# Consumer.net
KiCad netlist of a schematic drawn in Altium Designer
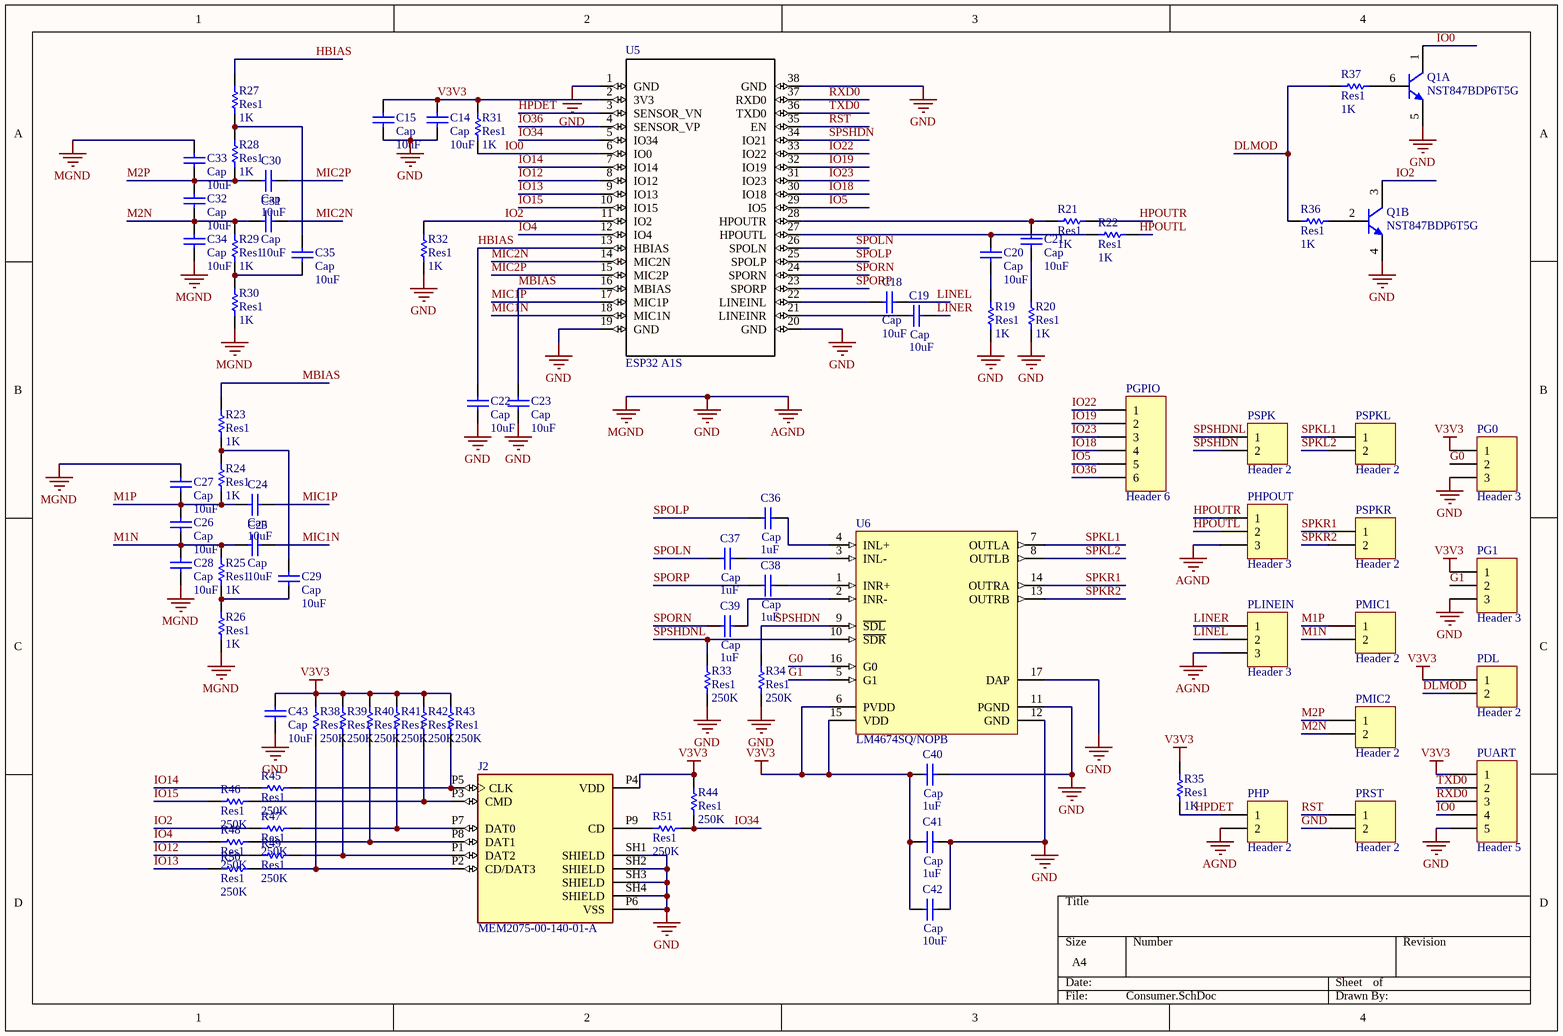
[diagram p0: Consumer.SchDoc]

(export (version "E")
  (design (tool "Eeschema 10.0.6"))
  (components
    (comp (ref "C14")
      (value "Cap")
      (footprint "1812")
      (description "Capacitor")
      (fields (field (name "ALTIUM_VALUE") "10uF") (field (name "PUBLISHER") "Altium Limited"))
      (libsource (lib "Miscellaneous Devices") (part "Cap"))
    )
    (comp (ref "C15")
      (value "Cap")
      (footprint "1608[0603]")
      (description "Capacitor")
      (fields (field (name "ALTIUM_VALUE") "10uF") (field (name "PUBLISHER") "Altium Limited"))
      (libsource (lib "Miscellaneous Devices") (part "Cap"))
    )
    (comp (ref "C18")
      (value "Cap")
      (footprint "1608[0603]")
      (description "Capacitor")
      (fields (field (name "ALTIUM_VALUE") "10uF") (field (name "PUBLISHER") "Altium Limited"))
      (libsource (lib "Miscellaneous Devices") (part "Cap"))
    )
    (comp (ref "C19")
      (value "Cap")
      (footprint "1608[0603]")
      (description "Capacitor")
      (fields (field (name "ALTIUM_VALUE") "10uF") (field (name "PUBLISHER") "Altium Limited"))
      (libsource (lib "Miscellaneous Devices") (part "Cap"))
    )
    (comp (ref "C20")
      (value "Cap")
      (footprint "1608[0603]")
      (description "Capacitor")
      (fields (field (name "ALTIUM_VALUE") "10uF") (field (name "PUBLISHER") "Altium Limited"))
      (libsource (lib "Miscellaneous Devices") (part "Cap"))
    )
    (comp (ref "C21")
      (value "Cap")
      (footprint "1608[0603]")
      (description "Capacitor")
      (fields (field (name "ALTIUM_VALUE") "10uF") (field (name "PUBLISHER") "Altium Limited"))
      (libsource (lib "Miscellaneous Devices") (part "Cap"))
    )
    (comp (ref "C22")
      (value "Cap")
      (footprint "1608[0603]")
      (description "Capacitor")
      (fields (field (name "ALTIUM_VALUE") "10uF") (field (name "PUBLISHER") "Altium Limited"))
      (libsource (lib "Miscellaneous Devices") (part "Cap"))
    )
    (comp (ref "C23")
      (value "Cap")
      (footprint "1608[0603]")
      (description "Capacitor")
      (fields (field (name "ALTIUM_VALUE") "10uF") (field (name "PUBLISHER") "Altium Limited"))
      (libsource (lib "Miscellaneous Devices") (part "Cap"))
    )
    (comp (ref "C24")
      (value "Cap")
      (footprint "1608[0603]")
      (description "Capacitor")
      (fields (field (name "ALTIUM_VALUE") "10uF") (field (name "PUBLISHER") "Altium Limited"))
      (libsource (lib "Miscellaneous Devices") (part "Cap"))
    )
    (comp (ref "C25")
      (value "Cap")
      (footprint "1608[0603]")
      (description "Capacitor")
      (fields (field (name "ALTIUM_VALUE") "10uF") (field (name "PUBLISHER") "Altium Limited"))
      (libsource (lib "Miscellaneous Devices") (part "Cap"))
    )
    (comp (ref "C26")
      (value "Cap")
      (footprint "1608[0603]")
      (description "Capacitor")
      (fields (field (name "ALTIUM_VALUE") "10uF") (field (name "PUBLISHER") "Altium Limited"))
      (libsource (lib "Miscellaneous Devices") (part "Cap"))
    )
    (comp (ref "C27")
      (value "Cap")
      (footprint "1608[0603]")
      (description "Capacitor")
      (fields (field (name "ALTIUM_VALUE") "10uF") (field (name "PUBLISHER") "Altium Limited"))
      (libsource (lib "Miscellaneous Devices") (part "Cap"))
    )
    (comp (ref "C28")
      (value "Cap")
      (footprint "1608[0603]")
      (description "Capacitor")
      (fields (field (name "ALTIUM_VALUE") "10uF") (field (name "PUBLISHER") "Altium Limited"))
      (libsource (lib "Miscellaneous Devices") (part "Cap"))
    )
    (comp (ref "C29")
      (value "Cap")
      (footprint "1608[0603]")
      (description "Capacitor")
      (fields (field (name "ALTIUM_VALUE") "10uF") (field (name "PUBLISHER") "Altium Limited"))
      (libsource (lib "Miscellaneous Devices") (part "Cap"))
    )
    (comp (ref "C30")
      (value "Cap")
      (footprint "1608[0603]")
      (description "Capacitor")
      (fields (field (name "ALTIUM_VALUE") "10uF") (field (name "PUBLISHER") "Altium Limited"))
      (libsource (lib "Miscellaneous Devices") (part "Cap"))
    )
    (comp (ref "C31")
      (value "Cap")
      (footprint "1608[0603]")
      (description "Capacitor")
      (fields (field (name "ALTIUM_VALUE") "10uF") (field (name "PUBLISHER") "Altium Limited"))
      (libsource (lib "Miscellaneous Devices") (part "Cap"))
    )
    (comp (ref "C32")
      (value "Cap")
      (footprint "1608[0603]")
      (description "Capacitor")
      (fields (field (name "ALTIUM_VALUE") "10uF") (field (name "PUBLISHER") "Altium Limited"))
      (libsource (lib "Miscellaneous Devices") (part "Cap"))
    )
    (comp (ref "C33")
      (value "Cap")
      (footprint "1608[0603]")
      (description "Capacitor")
      (fields (field (name "ALTIUM_VALUE") "10uF") (field (name "PUBLISHER") "Altium Limited"))
      (libsource (lib "Miscellaneous Devices") (part "Cap"))
    )
    (comp (ref "C34")
      (value "Cap")
      (footprint "1608[0603]")
      (description "Capacitor")
      (fields (field (name "ALTIUM_VALUE") "10uF") (field (name "PUBLISHER") "Altium Limited"))
      (libsource (lib "Miscellaneous Devices") (part "Cap"))
    )
    (comp (ref "C35")
      (value "Cap")
      (footprint "1608[0603]")
      (description "Capacitor")
      (fields (field (name "ALTIUM_VALUE") "10uF") (field (name "PUBLISHER") "Altium Limited"))
      (libsource (lib "Miscellaneous Devices") (part "Cap"))
    )
    (comp (ref "C36")
      (value "Cap")
      (footprint "1608[0603]")
      (description "Capacitor")
      (fields (field (name "ALTIUM_VALUE") "1uF") (field (name "PUBLISHER") "Altium Limited"))
      (libsource (lib "Miscellaneous Devices") (part "Cap"))
    )
    (comp (ref "C37")
      (value "Cap")
      (footprint "1608[0603]")
      (description "Capacitor")
      (fields (field (name "ALTIUM_VALUE") "1uF") (field (name "PUBLISHER") "Altium Limited"))
      (libsource (lib "Miscellaneous Devices") (part "Cap"))
    )
    (comp (ref "C38")
      (value "Cap")
      (footprint "1608[0603]")
      (description "Capacitor")
      (fields (field (name "ALTIUM_VALUE") "1uF") (field (name "PUBLISHER") "Altium Limited"))
      (libsource (lib "Miscellaneous Devices") (part "Cap"))
    )
    (comp (ref "C39")
      (value "Cap")
      (footprint "1608[0603]")
      (description "Capacitor")
      (fields (field (name "ALTIUM_VALUE") "1uF") (field (name "PUBLISHER") "Altium Limited"))
      (libsource (lib "Miscellaneous Devices") (part "Cap"))
    )
    (comp (ref "C40")
      (value "Cap")
      (footprint "1608[0603]")
      (description "Capacitor")
      (fields (field (name "ALTIUM_VALUE") "1uF") (field (name "PUBLISHER") "Altium Limited"))
      (libsource (lib "Miscellaneous Devices") (part "Cap"))
    )
    (comp (ref "C41")
      (value "Cap")
      (footprint "1608[0603]")
      (description "Capacitor")
      (fields (field (name "ALTIUM_VALUE") "1uF") (field (name "PUBLISHER") "Altium Limited"))
      (libsource (lib "Miscellaneous Devices") (part "Cap"))
    )
    (comp (ref "C42")
      (value "Cap")
      (footprint "1608[0603]")
      (description "Capacitor")
      (fields (field (name "ALTIUM_VALUE") "10uF") (field (name "PUBLISHER") "Altium Limited"))
      (libsource (lib "Miscellaneous Devices") (part "Cap"))
    )
    (comp (ref "C43")
      (value "Cap")
      (footprint "1608[0603]")
      (description "Capacitor")
      (fields (field (name "ALTIUM_VALUE") "10uF") (field (name "PUBLISHER") "Altium Limited"))
      (libsource (lib "Miscellaneous Devices") (part "Cap"))
    )
    (comp (ref "J2")
      (value "MEM2075-00-140-01-A")
      (footprint "GCT_MEM2075-00-140-01-A")
      (description "9 _8 + 1_ Position Card Connector microSDâ„¢ Surface Mount, Right Angle Gold")
      (fields (field (name "MF") "Global Connector Technology"))
      (libsource (lib "MEM2075-00-140-01-A") (part "MEM2075-00-140-01-A"))
    )
    (comp (ref "PDL")
      (value "Header 2")
      (footprint "HDR1X2")
      (description "Header, 2-Pin")
      (fields (field (name "PUBLISHER") "Altium Limited"))
      (libsource (lib "Miscellaneous Connectors") (part "Header 2"))
    )
    (comp (ref "PG0")
      (value "Header 3")
      (footprint "HDR1X3")
      (description "Header, 3-Pin")
      (fields (field (name "PUBLISHER") "Altium Limited"))
      (libsource (lib "Miscellaneous Connectors") (part "Header 3"))
    )
    (comp (ref "PG1")
      (value "Header 3")
      (footprint "HDR1X3")
      (description "Header, 3-Pin")
      (fields (field (name "PUBLISHER") "Altium Limited"))
      (libsource (lib "Miscellaneous Connectors") (part "Header 3"))
    )
    (comp (ref "PGPIO")
      (value "Header 6")
      (footprint "HDR1X6")
      (description "Header, 6-Pin")
      (fields (field (name "PUBLISHER") "Altium Limited"))
      (libsource (lib "Miscellaneous Connectors") (part "Header 6"))
    )
    (comp (ref "PHP")
      (value "Header 2")
      (footprint "HDR1X2")
      (description "Header, 2-Pin")
      (fields (field (name "PUBLISHER") "Altium Limited"))
      (libsource (lib "Miscellaneous Connectors") (part "Header 2"))
    )
    (comp (ref "PHPOUT")
      (value "Header 3")
      (footprint "HDR1X3")
      (description "Header, 3-Pin")
      (fields (field (name "PUBLISHER") "Altium Limited"))
      (libsource (lib "Miscellaneous Connectors") (part "Header 3"))
    )
    (comp (ref "PLINEIN")
      (value "Header 3")
      (footprint "HDR1X3")
      (description "Header, 3-Pin")
      (fields (field (name "PUBLISHER") "Altium Limited"))
      (libsource (lib "Miscellaneous Connectors") (part "Header 3"))
    )
    (comp (ref "PMIC1")
      (value "Header 2")
      (footprint "HDR1X2")
      (description "Header, 2-Pin")
      (fields (field (name "PUBLISHER") "Altium Limited"))
      (libsource (lib "Miscellaneous Connectors") (part "Header 2"))
    )
    (comp (ref "PMIC2")
      (value "Header 2")
      (footprint "HDR1X2")
      (description "Header, 2-Pin")
      (fields (field (name "PUBLISHER") "Altium Limited"))
      (libsource (lib "Miscellaneous Connectors") (part "Header 2"))
    )
    (comp (ref "PRST")
      (value "Header 2")
      (footprint "HDR1X2")
      (description "Header, 2-Pin")
      (fields (field (name "PUBLISHER") "Altium Limited"))
      (libsource (lib "Miscellaneous Connectors") (part "Header 2"))
    )
    (comp (ref "PSPK")
      (value "Header 2")
      (footprint "HDR1X2")
      (description "Header, 2-Pin")
      (fields (field (name "PUBLISHER") "Altium Limited"))
      (libsource (lib "Miscellaneous Connectors") (part "Header 2"))
    )
    (comp (ref "PSPKL")
      (value "Header 2")
      (footprint "HDR1X2")
      (description "Header, 2-Pin")
      (fields (field (name "PUBLISHER") "Altium Limited"))
      (libsource (lib "Miscellaneous Connectors") (part "Header 2"))
    )
    (comp (ref "PSPKR")
      (value "Header 2")
      (footprint "HDR1X2")
      (description "Header, 2-Pin")
      (fields (field (name "PUBLISHER") "Altium Limited"))
      (libsource (lib "Miscellaneous Connectors") (part "Header 2"))
    )
    (comp (ref "PUART")
      (value "Header 5")
      (footprint "HDR1X5")
      (description "Header, 5-Pin")
      (fields (field (name "PUBLISHER") "Altium Limited"))
      (libsource (lib "Miscellaneous Connectors") (part "Header 5"))
    )
    (comp (ref "Q1")
      (value "NST847BDP6T5G")
      (footprint "ONSC-SOT-963-6-527AD-01_B_V")
      (description "Dual General Purpose Transistors, 6-Pin SOT-963, Pb-Free, Tape and Reel")
      (fields (field (name "MANUFACTURER") "On Semiconductor"))
      (libsource (lib "Components - 31.05.21 - 11.16") (part "CMP-1048-01004-1"))
    )
    (comp (ref "R19")
      (value "Res1")
      (footprint "0603R-GENERIC")
      (description "Resistor")
      (fields (field (name "ALTIUM_VALUE") "1K") (field (name "PUBLISHER") "Altium Limited"))
      (libsource (lib "Miscellaneous Devices") (part "Res1"))
    )
    (comp (ref "R20")
      (value "Res1")
      (footprint "0603R-GENERIC")
      (description "Resistor")
      (fields (field (name "ALTIUM_VALUE") "1K") (field (name "PUBLISHER") "Altium Limited"))
      (libsource (lib "Miscellaneous Devices") (part "Res1"))
    )
    (comp (ref "R21")
      (value "Res1")
      (footprint "0603R-GENERIC")
      (description "Resistor")
      (fields (field (name "ALTIUM_VALUE") "1K") (field (name "PUBLISHER") "Altium Limited"))
      (libsource (lib "Miscellaneous Devices") (part "Res1"))
    )
    (comp (ref "R22")
      (value "Res1")
      (footprint "0603R-GENERIC")
      (description "Resistor")
      (fields (field (name "ALTIUM_VALUE") "1K") (field (name "PUBLISHER") "Altium Limited"))
      (libsource (lib "Miscellaneous Devices") (part "Res1"))
    )
    (comp (ref "R23")
      (value "Res1")
      (footprint "0603R-GENERIC")
      (description "Resistor")
      (fields (field (name "ALTIUM_VALUE") "1K") (field (name "PUBLISHER") "Altium Limited"))
      (libsource (lib "Miscellaneous Devices") (part "Res1"))
    )
    (comp (ref "R24")
      (value "Res1")
      (footprint "0603R-GENERIC")
      (description "Resistor")
      (fields (field (name "ALTIUM_VALUE") "1K") (field (name "PUBLISHER") "Altium Limited"))
      (libsource (lib "Miscellaneous Devices") (part "Res1"))
    )
    (comp (ref "R25")
      (value "Res1")
      (footprint "0603R-GENERIC")
      (description "Resistor")
      (fields (field (name "ALTIUM_VALUE") "1K") (field (name "PUBLISHER") "Altium Limited"))
      (libsource (lib "Miscellaneous Devices") (part "Res1"))
    )
    (comp (ref "R26")
      (value "Res1")
      (footprint "0603R-GENERIC")
      (description "Resistor")
      (fields (field (name "ALTIUM_VALUE") "1K") (field (name "PUBLISHER") "Altium Limited"))
      (libsource (lib "Miscellaneous Devices") (part "Res1"))
    )
    (comp (ref "R27")
      (value "Res1")
      (footprint "0603R-GENERIC")
      (description "Resistor")
      (fields (field (name "ALTIUM_VALUE") "1K") (field (name "PUBLISHER") "Altium Limited"))
      (libsource (lib "Miscellaneous Devices") (part "Res1"))
    )
    (comp (ref "R28")
      (value "Res1")
      (footprint "0603R-GENERIC")
      (description "Resistor")
      (fields (field (name "ALTIUM_VALUE") "1K") (field (name "PUBLISHER") "Altium Limited"))
      (libsource (lib "Miscellaneous Devices") (part "Res1"))
    )
    (comp (ref "R29")
      (value "Res1")
      (footprint "0603R-GENERIC")
      (description "Resistor")
      (fields (field (name "ALTIUM_VALUE") "1K") (field (name "PUBLISHER") "Altium Limited"))
      (libsource (lib "Miscellaneous Devices") (part "Res1"))
    )
    (comp (ref "R30")
      (value "Res1")
      (footprint "0603R-GENERIC")
      (description "Resistor")
      (fields (field (name "ALTIUM_VALUE") "1K") (field (name "PUBLISHER") "Altium Limited"))
      (libsource (lib "Miscellaneous Devices") (part "Res1"))
    )
    (comp (ref "R31")
      (value "Res1")
      (footprint "0603R-GENERIC")
      (description "Resistor")
      (fields (field (name "ALTIUM_VALUE") "1K") (field (name "PUBLISHER") "Altium Limited"))
      (libsource (lib "Miscellaneous Devices") (part "Res1"))
    )
    (comp (ref "R32")
      (value "Res1")
      (footprint "0603R-GENERIC")
      (description "Resistor")
      (fields (field (name "ALTIUM_VALUE") "1K") (field (name "PUBLISHER") "Altium Limited"))
      (libsource (lib "Miscellaneous Devices") (part "Res1"))
    )
    (comp (ref "R33")
      (value "Res1")
      (footprint "0603R-GENERIC")
      (description "Resistor")
      (fields (field (name "ALTIUM_VALUE") "250K") (field (name "PUBLISHER") "Altium Limited"))
      (libsource (lib "Miscellaneous Devices") (part "Res1"))
    )
    (comp (ref "R34")
      (value "Res1")
      (footprint "0603R-GENERIC")
      (description "Resistor")
      (fields (field (name "ALTIUM_VALUE") "250K") (field (name "PUBLISHER") "Altium Limited"))
      (libsource (lib "Miscellaneous Devices") (part "Res1"))
    )
    (comp (ref "R35")
      (value "Res1")
      (footprint "0603R-GENERIC")
      (description "Resistor")
      (fields (field (name "ALTIUM_VALUE") "1K") (field (name "PUBLISHER") "Altium Limited"))
      (libsource (lib "Miscellaneous Devices") (part "Res1"))
    )
    (comp (ref "R36")
      (value "Res1")
      (footprint "0603R-GENERIC")
      (description "Resistor")
      (fields (field (name "ALTIUM_VALUE") "1K") (field (name "PUBLISHER") "Altium Limited"))
      (libsource (lib "Miscellaneous Devices") (part "Res1"))
    )
    (comp (ref "R37")
      (value "Res1")
      (footprint "0603R-GENERIC")
      (description "Resistor")
      (fields (field (name "ALTIUM_VALUE") "1K") (field (name "PUBLISHER") "Altium Limited"))
      (libsource (lib "Miscellaneous Devices") (part "Res1"))
    )
    (comp (ref "R38")
      (value "Res1")
      (footprint "0603R-GENERIC")
      (description "Resistor")
      (fields (field (name "ALTIUM_VALUE") "250K") (field (name "PUBLISHER") "Altium Limited"))
      (libsource (lib "Miscellaneous Devices") (part "Res1"))
    )
    (comp (ref "R39")
      (value "Res1")
      (footprint "0603R-GENERIC")
      (description "Resistor")
      (fields (field (name "ALTIUM_VALUE") "250K") (field (name "PUBLISHER") "Altium Limited"))
      (libsource (lib "Miscellaneous Devices") (part "Res1"))
    )
    (comp (ref "R40")
      (value "Res1")
      (footprint "0603R-GENERIC")
      (description "Resistor")
      (fields (field (name "ALTIUM_VALUE") "250K") (field (name "PUBLISHER") "Altium Limited"))
      (libsource (lib "Miscellaneous Devices") (part "Res1"))
    )
    (comp (ref "R41")
      (value "Res1")
      (footprint "0603R-GENERIC")
      (description "Resistor")
      (fields (field (name "ALTIUM_VALUE") "250K") (field (name "PUBLISHER") "Altium Limited"))
      (libsource (lib "Miscellaneous Devices") (part "Res1"))
    )
    (comp (ref "R42")
      (value "Res1")
      (footprint "0603R-GENERIC")
      (description "Resistor")
      (fields (field (name "ALTIUM_VALUE") "250K") (field (name "PUBLISHER") "Altium Limited"))
      (libsource (lib "Miscellaneous Devices") (part "Res1"))
    )
    (comp (ref "R43")
      (value "Res1")
      (footprint "0603R-GENERIC")
      (description "Resistor")
      (fields (field (name "ALTIUM_VALUE") "250K") (field (name "PUBLISHER") "Altium Limited"))
      (libsource (lib "Miscellaneous Devices") (part "Res1"))
    )
    (comp (ref "R44")
      (value "Res1")
      (footprint "0603R-GENERIC")
      (description "Resistor")
      (fields (field (name "ALTIUM_VALUE") "250K") (field (name "PUBLISHER") "Altium Limited"))
      (libsource (lib "Miscellaneous Devices") (part "Res1"))
    )
    (comp (ref "R45")
      (value "Res1")
      (footprint "0603R-GENERIC")
      (description "Resistor")
      (fields (field (name "ALTIUM_VALUE") "250K") (field (name "PUBLISHER") "Altium Limited"))
      (libsource (lib "Miscellaneous Devices") (part "Res1"))
    )
    (comp (ref "R46")
      (value "Res1")
      (footprint "0603R-GENERIC")
      (description "Resistor")
      (fields (field (name "ALTIUM_VALUE") "250K") (field (name "PUBLISHER") "Altium Limited"))
      (libsource (lib "Miscellaneous Devices") (part "Res1"))
    )
    (comp (ref "R47")
      (value "Res1")
      (footprint "0603R-GENERIC")
      (description "Resistor")
      (fields (field (name "ALTIUM_VALUE") "250K") (field (name "PUBLISHER") "Altium Limited"))
      (libsource (lib "Miscellaneous Devices") (part "Res1"))
    )
    (comp (ref "R48")
      (value "Res1")
      (footprint "0603R-GENERIC")
      (description "Resistor")
      (fields (field (name "ALTIUM_VALUE") "250K") (field (name "PUBLISHER") "Altium Limited"))
      (libsource (lib "Miscellaneous Devices") (part "Res1"))
    )
    (comp (ref "R49")
      (value "Res1")
      (footprint "0603R-GENERIC")
      (description "Resistor")
      (fields (field (name "ALTIUM_VALUE") "250K") (field (name "PUBLISHER") "Altium Limited"))
      (libsource (lib "Miscellaneous Devices") (part "Res1"))
    )
    (comp (ref "R50")
      (value "Res1")
      (footprint "0603R-GENERIC")
      (description "Resistor")
      (fields (field (name "ALTIUM_VALUE") "250K") (field (name "PUBLISHER") "Altium Limited"))
      (libsource (lib "Miscellaneous Devices") (part "Res1"))
    )
    (comp (ref "R51")
      (value "Res1")
      (footprint "0603R-GENERIC")
      (description "Resistor")
      (fields (field (name "ALTIUM_VALUE") "250K") (field (name "PUBLISHER") "Altium Limited"))
      (libsource (lib "Miscellaneous Devices") (part "Res1"))
    )
    (comp (ref "U5")
      (value "ESP32 A1S")
      (footprint "ESP32 A1S")
      (fields (field (name "MP") "SAMTEC-FTS-110-01-X-S"))
      (libsource (lib "ESP32-A1S") (part "ESP32 A1S"))
    )
    (comp (ref "U6")
      (value "LM4674SQ/NOPB")
      (footprint "RGH0016A_V")
      (description "Filterless 2.5 Stereo Class D Audio Power Amplifier, 16-pin LLP, Pb-Free")
      (fields (field (name "MANUFACTURER") "Texas Instruments"))
      (libsource (lib "Altium Content Vault") (part "AMP-APA-LM4674-17"))
    )
  )
  (nets
    (net (code "1") (name "/DLMOD") (class "Default")
      (node (ref "PDL") (pin "2") (pinfunction "2_2") (pintype "passive"))
      (node (ref "R36") (pin "2") (pinfunction "2_2") (pintype "passive"))
      (node (ref "R37") (pin "2") (pinfunction "2_2") (pintype "passive"))
    )
    (net (code "2") (name "/G0") (class "Default")
      (node (ref "PG0") (pin "2") (pinfunction "2_2") (pintype "passive"))
      (node (ref "U6") (pin "16") (pinfunction "G0_16") (pintype "input"))
    )
    (net (code "3") (name "/G1") (class "Default")
      (node (ref "PG1") (pin "2") (pinfunction "2_2") (pintype "passive"))
      (node (ref "U6") (pin "5") (pinfunction "G1_5") (pintype "input"))
    )
    (net (code "4") (name "/HBIAS") (class "Default")
      (node (ref "C22") (pin "2") (pinfunction "2_2") (pintype "passive"))
      (node (ref "R27") (pin "1") (pinfunction "1_1") (pintype "passive"))
      (node (ref "U5") (pin "13") (pinfunction "HBIAS_13") (pintype "bidirectional"))
    )
    (net (code "5") (name "/HPDET") (class "Default")
      (node (ref "PHP") (pin "1") (pinfunction "1_1") (pintype "passive"))
      (node (ref "R35") (pin "2") (pinfunction "2_2") (pintype "passive"))
      (node (ref "U5") (pin "3") (pinfunction "SENSOR_VN_3") (pintype "bidirectional"))
    )
    (net (code "6") (name "/HPOUTL") (class "Default")
      (node (ref "PHPOUT") (pin "2") (pinfunction "2_2") (pintype "passive"))
      (node (ref "R22") (pin "1") (pinfunction "1_1") (pintype "passive"))
    )
    (net (code "7") (name "/HPOUTR") (class "Default")
      (node (ref "PHPOUT") (pin "1") (pinfunction "1_1") (pintype "passive"))
      (node (ref "R21") (pin "1") (pinfunction "1_1") (pintype "passive"))
    )
    (net (code "8") (name "/IO0") (class "Default")
      (node (ref "PUART") (pin "4") (pinfunction "4_4") (pintype "passive"))
      (node (ref "Q1") (pin "1") (pinfunction "C_1") (pintype "passive"))
      (node (ref "R31") (pin "2") (pinfunction "2_2") (pintype "passive"))
      (node (ref "U5") (pin "6") (pinfunction "IO0_6") (pintype "bidirectional"))
    )
    (net (code "9") (name "/IO2") (class "Default")
      (node (ref "Q1") (pin "3") (pinfunction "C_3") (pintype "passive"))
      (node (ref "R32") (pin "1") (pinfunction "1_1") (pintype "passive"))
      (node (ref "R47") (pin "1") (pinfunction "1_1") (pintype "passive"))
      (node (ref "U5") (pin "11") (pinfunction "IO2_11") (pintype "bidirectional"))
    )
    (net (code "10") (name "/IO4") (class "Default")
      (node (ref "R48") (pin "1") (pinfunction "1_1") (pintype "passive"))
      (node (ref "U5") (pin "12") (pinfunction "IO4_12") (pintype "bidirectional"))
    )
    (net (code "11") (name "/IO5") (class "Default")
      (node (ref "PGPIO") (pin "5") (pinfunction "5_5") (pintype "passive"))
      (node (ref "U5") (pin "29") (pinfunction "IO5_29") (pintype "bidirectional"))
    )
    (net (code "12") (name "/IO12") (class "Default")
      (node (ref "R49") (pin "1") (pinfunction "1_1") (pintype "passive"))
      (node (ref "U5") (pin "8") (pinfunction "IO12_8") (pintype "bidirectional"))
    )
    (net (code "13") (name "/IO13") (class "Default")
      (node (ref "R50") (pin "1") (pinfunction "1_1") (pintype "passive"))
      (node (ref "U5") (pin "9") (pinfunction "IO13_9") (pintype "bidirectional"))
    )
    (net (code "14") (name "/IO14") (class "Default")
      (node (ref "R45") (pin "1") (pinfunction "1_1") (pintype "passive"))
      (node (ref "U5") (pin "7") (pinfunction "IO14_7") (pintype "bidirectional"))
    )
    (net (code "15") (name "/IO15") (class "Default")
      (node (ref "R46") (pin "1") (pinfunction "1_1") (pintype "passive"))
      (node (ref "U5") (pin "10") (pinfunction "IO15_10") (pintype "bidirectional"))
    )
    (net (code "16") (name "/IO18") (class "Default")
      (node (ref "PGPIO") (pin "4") (pinfunction "4_4") (pintype "passive"))
      (node (ref "U5") (pin "30") (pinfunction "IO18_30") (pintype "bidirectional"))
    )
    (net (code "17") (name "/IO19") (class "Default")
      (node (ref "PGPIO") (pin "2") (pinfunction "2_2") (pintype "passive"))
      (node (ref "U5") (pin "32") (pinfunction "IO19_32") (pintype "bidirectional"))
    )
    (net (code "18") (name "/IO22") (class "Default")
      (node (ref "PGPIO") (pin "1") (pinfunction "1_1") (pintype "passive"))
      (node (ref "U5") (pin "33") (pinfunction "IO22_33") (pintype "bidirectional"))
    )
    (net (code "19") (name "/IO23") (class "Default")
      (node (ref "PGPIO") (pin "3") (pinfunction "3_3") (pintype "passive"))
      (node (ref "U5") (pin "31") (pinfunction "IO23_31") (pintype "bidirectional"))
    )
    (net (code "20") (name "/IO34") (class "Default")
      (node (ref "R44") (pin "2") (pinfunction "2_2") (pintype "passive"))
      (node (ref "R51") (pin "2") (pinfunction "2_2") (pintype "passive"))
      (node (ref "U5") (pin "5") (pinfunction "IO34_5") (pintype "bidirectional"))
    )
    (net (code "21") (name "/IO36") (class "Default")
      (node (ref "PGPIO") (pin "6") (pinfunction "6_6") (pintype "passive"))
      (node (ref "U5") (pin "4") (pinfunction "SENSOR_VP_4") (pintype "bidirectional"))
    )
    (net (code "22") (name "/LINEL") (class "Default")
      (node (ref "C18") (pin "1") (pinfunction "1_1") (pintype "passive"))
      (node (ref "PLINEIN") (pin "2") (pinfunction "2_2") (pintype "passive"))
    )
    (net (code "23") (name "/LINER") (class "Default")
      (node (ref "C19") (pin "1") (pinfunction "1_1") (pintype "passive"))
      (node (ref "PLINEIN") (pin "1") (pinfunction "1_1") (pintype "passive"))
    )
    (net (code "24") (name "/M1N") (class "Default")
      (node (ref "C25") (pin "2") (pinfunction "2_2") (pintype "passive"))
      (node (ref "C26") (pin "2") (pinfunction "2_2") (pintype "passive"))
      (node (ref "C28") (pin "1") (pinfunction "1_1") (pintype "passive"))
      (node (ref "PMIC1") (pin "2") (pinfunction "2_2") (pintype "passive"))
      (node (ref "R25") (pin "1") (pinfunction "1_1") (pintype "passive"))
    )
    (net (code "25") (name "/M1P") (class "Default")
      (node (ref "C24") (pin "2") (pinfunction "2_2") (pintype "passive"))
      (node (ref "C26") (pin "1") (pinfunction "1_1") (pintype "passive"))
      (node (ref "C27") (pin "2") (pinfunction "2_2") (pintype "passive"))
      (node (ref "PMIC1") (pin "1") (pinfunction "1_1") (pintype "passive"))
      (node (ref "R24") (pin "2") (pinfunction "2_2") (pintype "passive"))
    )
    (net (code "26") (name "/M2N") (class "Default")
      (node (ref "C31") (pin "2") (pinfunction "2_2") (pintype "passive"))
      (node (ref "C32") (pin "2") (pinfunction "2_2") (pintype "passive"))
      (node (ref "C34") (pin "1") (pinfunction "1_1") (pintype "passive"))
      (node (ref "PMIC2") (pin "2") (pinfunction "2_2") (pintype "passive"))
      (node (ref "R29") (pin "1") (pinfunction "1_1") (pintype "passive"))
    )
    (net (code "27") (name "/M2P") (class "Default")
      (node (ref "C30") (pin "2") (pinfunction "2_2") (pintype "passive"))
      (node (ref "C32") (pin "1") (pinfunction "1_1") (pintype "passive"))
      (node (ref "C33") (pin "2") (pinfunction "2_2") (pintype "passive"))
      (node (ref "PMIC2") (pin "1") (pinfunction "1_1") (pintype "passive"))
      (node (ref "R28") (pin "2") (pinfunction "2_2") (pintype "passive"))
    )
    (net (code "28") (name "/MBIAS") (class "Default")
      (node (ref "C23") (pin "2") (pinfunction "2_2") (pintype "passive"))
      (node (ref "R23") (pin "1") (pinfunction "1_1") (pintype "passive"))
      (node (ref "U5") (pin "16") (pinfunction "MBIAS_16") (pintype "bidirectional"))
    )
    (net (code "29") (name "/MIC1N") (class "Default")
      (node (ref "C25") (pin "1") (pinfunction "1_1") (pintype "passive"))
      (node (ref "U5") (pin "18") (pinfunction "MIC1N_18") (pintype "bidirectional"))
    )
    (net (code "30") (name "/MIC1P") (class "Default")
      (node (ref "C24") (pin "1") (pinfunction "1_1") (pintype "passive"))
      (node (ref "U5") (pin "17") (pinfunction "MIC1P_17") (pintype "bidirectional"))
    )
    (net (code "31") (name "/MIC2N") (class "Default")
      (node (ref "C31") (pin "1") (pinfunction "1_1") (pintype "passive"))
      (node (ref "U5") (pin "14") (pinfunction "MIC2N_14") (pintype "bidirectional"))
    )
    (net (code "32") (name "/MIC2P") (class "Default")
      (node (ref "C30") (pin "1") (pinfunction "1_1") (pintype "passive"))
      (node (ref "U5") (pin "15") (pinfunction "MIC2P_15") (pintype "bidirectional"))
    )
    (net (code "33") (name "/RST") (class "Default")
      (node (ref "PRST") (pin "1") (pinfunction "1_1") (pintype "passive"))
      (node (ref "U5") (pin "35") (pinfunction "EN_35") (pintype "bidirectional"))
    )
    (net (code "34") (name "/RXD0") (class "Default")
      (node (ref "PUART") (pin "3") (pinfunction "3_3") (pintype "passive"))
      (node (ref "U5") (pin "37") (pinfunction "RXD0_37") (pintype "bidirectional"))
    )
    (net (code "35") (name "/SPKL1") (class "Default")
      (node (ref "PSPKL") (pin "1") (pinfunction "1_1") (pintype "passive"))
      (node (ref "U6") (pin "7") (pinfunction "OUTLA_7") (pintype "output"))
    )
    (net (code "36") (name "/SPKL2") (class "Default")
      (node (ref "PSPKL") (pin "2") (pinfunction "2_2") (pintype "passive"))
      (node (ref "U6") (pin "8") (pinfunction "OUTLB_8") (pintype "output"))
    )
    (net (code "37") (name "/SPKR1") (class "Default")
      (node (ref "PSPKR") (pin "1") (pinfunction "1_1") (pintype "passive"))
      (node (ref "U6") (pin "14") (pinfunction "OUTRA_14") (pintype "output"))
    )
    (net (code "38") (name "/SPKR2") (class "Default")
      (node (ref "PSPKR") (pin "2") (pinfunction "2_2") (pintype "passive"))
      (node (ref "U6") (pin "13") (pinfunction "OUTRB_13") (pintype "output"))
    )
    (net (code "39") (name "/SPOLN") (class "Default")
      (node (ref "C37") (pin "2") (pinfunction "2_2") (pintype "passive"))
      (node (ref "U5") (pin "26") (pinfunction "SPOLN_26") (pintype "bidirectional"))
    )
    (net (code "40") (name "/SPOLP") (class "Default")
      (node (ref "C36") (pin "2") (pinfunction "2_2") (pintype "passive"))
      (node (ref "U5") (pin "25") (pinfunction "SPOLP_25") (pintype "bidirectional"))
    )
    (net (code "41") (name "/SPORN") (class "Default")
      (node (ref "C39") (pin "2") (pinfunction "2_2") (pintype "passive"))
      (node (ref "U5") (pin "24") (pinfunction "SPORN_24") (pintype "bidirectional"))
    )
    (net (code "42") (name "/SPORP") (class "Default")
      (node (ref "C38") (pin "2") (pinfunction "2_2") (pintype "passive"))
      (node (ref "U5") (pin "23") (pinfunction "SPORP_23") (pintype "bidirectional"))
    )
    (net (code "43") (name "/SPSHDN") (class "Default")
      (node (ref "PSPK") (pin "2") (pinfunction "2_2") (pintype "passive"))
      (node (ref "R34") (pin "1") (pinfunction "1_1") (pintype "passive"))
      (node (ref "U5") (pin "34") (pinfunction "IO21_34") (pintype "bidirectional"))
      (node (ref "U6") (pin "9") (pinfunction "~{SDL}_9") (pintype "input"))
    )
    (net (code "44") (name "/SPSHDNL") (class "Default")
      (node (ref "PSPK") (pin "1") (pinfunction "1_1") (pintype "passive"))
      (node (ref "R33") (pin "1") (pinfunction "1_1") (pintype "passive"))
      (node (ref "U6") (pin "10") (pinfunction "~{SDR}_10") (pintype "input"))
    )
    (net (code "45") (name "/TXD0") (class "Default")
      (node (ref "PUART") (pin "2") (pinfunction "2_2") (pintype "passive"))
      (node (ref "U5") (pin "36") (pinfunction "TXD0_36") (pintype "bidirectional"))
    )
    (net (code "46") (name "AGND") (class "Default")
      (node (ref "C14") (pin "1") (pinfunction "1_1") (pintype "passive"))
      (node (ref "C15") (pin "1") (pinfunction "1_1") (pintype "passive"))
      (node (ref "C22") (pin "1") (pinfunction "1_1") (pintype "passive"))
      (node (ref "C23") (pin "1") (pinfunction "1_1") (pintype "passive"))
      (node (ref "C27") (pin "1") (pinfunction "1_1") (pintype "passive"))
      (node (ref "C28") (pin "2") (pinfunction "2_2") (pintype "passive"))
      (node (ref "C33") (pin "1") (pinfunction "1_1") (pintype "passive"))
      (node (ref "C34") (pin "2") (pinfunction "2_2") (pintype "passive"))
      (node (ref "C40") (pin "1") (pinfunction "1_1") (pintype "passive"))
      (node (ref "C41") (pin "1") (pinfunction "1_1") (pintype "passive"))
      (node (ref "C42") (pin "1") (pinfunction "1_1") (pintype "passive"))
      (node (ref "C43") (pin "2") (pinfunction "2_2") (pintype "passive"))
      (node (ref "J2") (pin "P6") (pinfunction "VSS_P6") (pintype "power_in"))
      (node (ref "J2") (pin "SH1") (pinfunction "SHIELD_SH1") (pintype "power_in"))
      (node (ref "J2") (pin "SH2") (pinfunction "SHIELD_SH2") (pintype "power_in"))
      (node (ref "J2") (pin "SH3") (pinfunction "SHIELD_SH3") (pintype "power_in"))
      (node (ref "J2") (pin "SH4") (pinfunction "SHIELD_SH4") (pintype "power_in"))
      (node (ref "PG0") (pin "3") (pinfunction "3_3") (pintype "passive"))
      (node (ref "PG1") (pin "3") (pinfunction "3_3") (pintype "passive"))
      (node (ref "PHP") (pin "2") (pinfunction "2_2") (pintype "passive"))
      (node (ref "PHPOUT") (pin "3") (pinfunction "3_3") (pintype "passive"))
      (node (ref "PLINEIN") (pin "3") (pinfunction "3_3") (pintype "passive"))
      (node (ref "PRST") (pin "2") (pinfunction "2_2") (pintype "passive"))
      (node (ref "PUART") (pin "5") (pinfunction "5_5") (pintype "passive"))
      (node (ref "Q1") (pin "4") (pinfunction "E_4") (pintype "passive"))
      (node (ref "Q1") (pin "5") (pinfunction "E_5") (pintype "passive"))
      (node (ref "R19") (pin "2") (pinfunction "2_2") (pintype "passive"))
      (node (ref "R20") (pin "1") (pinfunction "1_1") (pintype "passive"))
      (node (ref "R26") (pin "2") (pinfunction "2_2") (pintype "passive"))
      (node (ref "R30") (pin "2") (pinfunction "2_2") (pintype "passive"))
      (node (ref "R32") (pin "2") (pinfunction "2_2") (pintype "passive"))
      (node (ref "R33") (pin "2") (pinfunction "2_2") (pintype "passive"))
      (node (ref "R34") (pin "2") (pinfunction "2_2") (pintype "passive"))
      (node (ref "U5") (pin "1") (pinfunction "GND_1") (pintype "bidirectional"))
      (node (ref "U5") (pin "19") (pinfunction "GND_19") (pintype "bidirectional"))
      (node (ref "U5") (pin "20") (pinfunction "GND_20") (pintype "bidirectional"))
      (node (ref "U5") (pin "38") (pinfunction "GND_38") (pintype "bidirectional"))
      (node (ref "U6") (pin "11") (pinfunction "PGND_11") (pintype "power_in"))
      (node (ref "U6") (pin "12") (pinfunction "GND_12") (pintype "power_in"))
      (node (ref "U6") (pin "17") (pinfunction "DAP_17") (pintype "power_in"))
    )
    (net (code "47") (name "Net-(C20-Pad1)") (class "Default")
      (node (ref "C20") (pin "1") (pinfunction "1_1") (pintype "passive"))
      (node (ref "R19") (pin "1") (pinfunction "1_1") (pintype "passive"))
    )
    (net (code "48") (name "Net-(C21-Pad1)") (class "Default")
      (node (ref "C21") (pin "1") (pinfunction "1_1") (pintype "passive"))
      (node (ref "R20") (pin "2") (pinfunction "2_2") (pintype "passive"))
    )
    (net (code "49") (name "Net-(C29-Pad1)") (class "Default")
      (node (ref "C29") (pin "1") (pinfunction "1_1") (pintype "passive"))
      (node (ref "R23") (pin "2") (pinfunction "2_2") (pintype "passive"))
      (node (ref "R24") (pin "1") (pinfunction "1_1") (pintype "passive"))
    )
    (net (code "50") (name "Net-(C29-Pad2)") (class "Default")
      (node (ref "C29") (pin "2") (pinfunction "2_2") (pintype "passive"))
      (node (ref "R25") (pin "2") (pinfunction "2_2") (pintype "passive"))
      (node (ref "R26") (pin "1") (pinfunction "1_1") (pintype "passive"))
    )
    (net (code "51") (name "Net-(C35-Pad1)") (class "Default")
      (node (ref "C35") (pin "1") (pinfunction "1_1") (pintype "passive"))
      (node (ref "R27") (pin "2") (pinfunction "2_2") (pintype "passive"))
      (node (ref "R28") (pin "1") (pinfunction "1_1") (pintype "passive"))
    )
    (net (code "52") (name "Net-(C35-Pad2)") (class "Default")
      (node (ref "C35") (pin "2") (pinfunction "2_2") (pintype "passive"))
      (node (ref "R29") (pin "2") (pinfunction "2_2") (pintype "passive"))
      (node (ref "R30") (pin "1") (pinfunction "1_1") (pintype "passive"))
    )
    (net (code "53") (name "Net-(J2-CD)") (class "Default")
      (node (ref "J2") (pin "P9") (pinfunction "CD_P9") (pintype "passive"))
      (node (ref "R51") (pin "1") (pinfunction "1_1") (pintype "passive"))
    )
    (net (code "54") (name "Net-(J2-CD{slash}DAT3)") (class "Default")
      (node (ref "J2") (pin "P2") (pinfunction "CD/DAT3_P2") (pintype "bidirectional"))
      (node (ref "R38") (pin "2") (pinfunction "2_2") (pintype "passive"))
      (node (ref "R50") (pin "2") (pinfunction "2_2") (pintype "passive"))
    )
    (net (code "55") (name "Net-(J2-CLK)") (class "Default")
      (node (ref "J2") (pin "P5") (pinfunction "CLK_P5") (pintype "bidirectional"))
      (node (ref "R43") (pin "2") (pinfunction "2_2") (pintype "passive"))
      (node (ref "R45") (pin "2") (pinfunction "2_2") (pintype "passive"))
    )
    (net (code "56") (name "Net-(J2-CMD)") (class "Default")
      (node (ref "J2") (pin "P3") (pinfunction "CMD_P3") (pintype "bidirectional"))
      (node (ref "R42") (pin "2") (pinfunction "2_2") (pintype "passive"))
      (node (ref "R46") (pin "2") (pinfunction "2_2") (pintype "passive"))
    )
    (net (code "57") (name "Net-(J2-DAT0)") (class "Default")
      (node (ref "J2") (pin "P7") (pinfunction "DAT0_P7") (pintype "bidirectional"))
      (node (ref "R41") (pin "2") (pinfunction "2_2") (pintype "passive"))
      (node (ref "R47") (pin "2") (pinfunction "2_2") (pintype "passive"))
    )
    (net (code "58") (name "Net-(J2-DAT1)") (class "Default")
      (node (ref "J2") (pin "P8") (pinfunction "DAT1_P8") (pintype "bidirectional"))
      (node (ref "R40") (pin "2") (pinfunction "2_2") (pintype "passive"))
      (node (ref "R48") (pin "2") (pinfunction "2_2") (pintype "passive"))
    )
    (net (code "59") (name "Net-(J2-DAT2)") (class "Default")
      (node (ref "J2") (pin "P1") (pinfunction "DAT2_P1") (pintype "bidirectional"))
      (node (ref "R39") (pin "2") (pinfunction "2_2") (pintype "passive"))
      (node (ref "R49") (pin "2") (pinfunction "2_2") (pintype "passive"))
    )
    (net (code "60") (name "Net-(Q1A-B)") (class "Default")
      (node (ref "Q1") (pin "6") (pinfunction "B_6") (pintype "passive"))
      (node (ref "R37") (pin "1") (pinfunction "1_1") (pintype "passive"))
    )
    (net (code "61") (name "Net-(Q1B-B)") (class "Default")
      (node (ref "Q1") (pin "2") (pinfunction "B_2") (pintype "passive"))
      (node (ref "R36") (pin "1") (pinfunction "1_1") (pintype "passive"))
    )
    (net (code "62") (name "Net-(U5-HPOUTL)") (class "Default")
      (node (ref "C20") (pin "2") (pinfunction "2_2") (pintype "passive"))
      (node (ref "R22") (pin "2") (pinfunction "2_2") (pintype "passive"))
      (node (ref "U5") (pin "27") (pinfunction "HPOUTL_27") (pintype "bidirectional"))
    )
    (net (code "63") (name "Net-(U5-HPOUTR)") (class "Default")
      (node (ref "C21") (pin "2") (pinfunction "2_2") (pintype "passive"))
      (node (ref "R21") (pin "2") (pinfunction "2_2") (pintype "passive"))
      (node (ref "U5") (pin "28") (pinfunction "HPOUTR_28") (pintype "bidirectional"))
    )
    (net (code "64") (name "Net-(U5-LINEINL)") (class "Default")
      (node (ref "C18") (pin "2") (pinfunction "2_2") (pintype "passive"))
      (node (ref "U5") (pin "22") (pinfunction "LINEINL_22") (pintype "bidirectional"))
    )
    (net (code "65") (name "Net-(U5-LINEINR)") (class "Default")
      (node (ref "C19") (pin "2") (pinfunction "2_2") (pintype "passive"))
      (node (ref "U5") (pin "21") (pinfunction "LINEINR_21") (pintype "bidirectional"))
    )
    (net (code "66") (name "Net-(U6-INL+)") (class "Default")
      (node (ref "C36") (pin "1") (pinfunction "1_1") (pintype "passive"))
      (node (ref "U6") (pin "4") (pinfunction "INL+_4") (pintype "input"))
    )
    (net (code "67") (name "Net-(U6-INL-)") (class "Default")
      (node (ref "C37") (pin "1") (pinfunction "1_1") (pintype "passive"))
      (node (ref "U6") (pin "3") (pinfunction "INL-_3") (pintype "input"))
    )
    (net (code "68") (name "Net-(U6-INR+)") (class "Default")
      (node (ref "C38") (pin "1") (pinfunction "1_1") (pintype "passive"))
      (node (ref "U6") (pin "1") (pinfunction "INR+_1") (pintype "input"))
    )
    (net (code "69") (name "Net-(U6-INR-)") (class "Default")
      (node (ref "C39") (pin "1") (pinfunction "1_1") (pintype "passive"))
      (node (ref "U6") (pin "2") (pinfunction "INR-_2") (pintype "input"))
    )
    (net (code "70") (name "V3V3") (class "Default")
      (node (ref "C14") (pin "2") (pinfunction "2_2") (pintype "passive"))
      (node (ref "C15") (pin "2") (pinfunction "2_2") (pintype "passive"))
      (node (ref "C40") (pin "2") (pinfunction "2_2") (pintype "passive"))
      (node (ref "C41") (pin "2") (pinfunction "2_2") (pintype "passive"))
      (node (ref "C42") (pin "2") (pinfunction "2_2") (pintype "passive"))
      (node (ref "C43") (pin "1") (pinfunction "1_1") (pintype "passive"))
      (node (ref "J2") (pin "P4") (pinfunction "VDD_P4") (pintype "power_in"))
      (node (ref "PDL") (pin "1") (pinfunction "1_1") (pintype "passive"))
      (node (ref "PG0") (pin "1") (pinfunction "1_1") (pintype "passive"))
      (node (ref "PG1") (pin "1") (pinfunction "1_1") (pintype "passive"))
      (node (ref "PUART") (pin "1") (pinfunction "1_1") (pintype "passive"))
      (node (ref "R31") (pin "1") (pinfunction "1_1") (pintype "passive"))
      (node (ref "R35") (pin "1") (pinfunction "1_1") (pintype "passive"))
      (node (ref "R38") (pin "1") (pinfunction "1_1") (pintype "passive"))
      (node (ref "R39") (pin "1") (pinfunction "1_1") (pintype "passive"))
      (node (ref "R40") (pin "1") (pinfunction "1_1") (pintype "passive"))
      (node (ref "R41") (pin "1") (pinfunction "1_1") (pintype "passive"))
      (node (ref "R42") (pin "1") (pinfunction "1_1") (pintype "passive"))
      (node (ref "R43") (pin "1") (pinfunction "1_1") (pintype "passive"))
      (node (ref "R44") (pin "1") (pinfunction "1_1") (pintype "passive"))
      (node (ref "U5") (pin "2") (pinfunction "3V3_2") (pintype "bidirectional"))
      (node (ref "U6") (pin "15") (pinfunction "VDD_15") (pintype "power_in"))
      (node (ref "U6") (pin "6") (pinfunction "PVDD_6") (pintype "power_in"))
    )
  )
)
